# Programmable_DC_Load.net
KiCad netlist of a schematic drawn in EAGLE
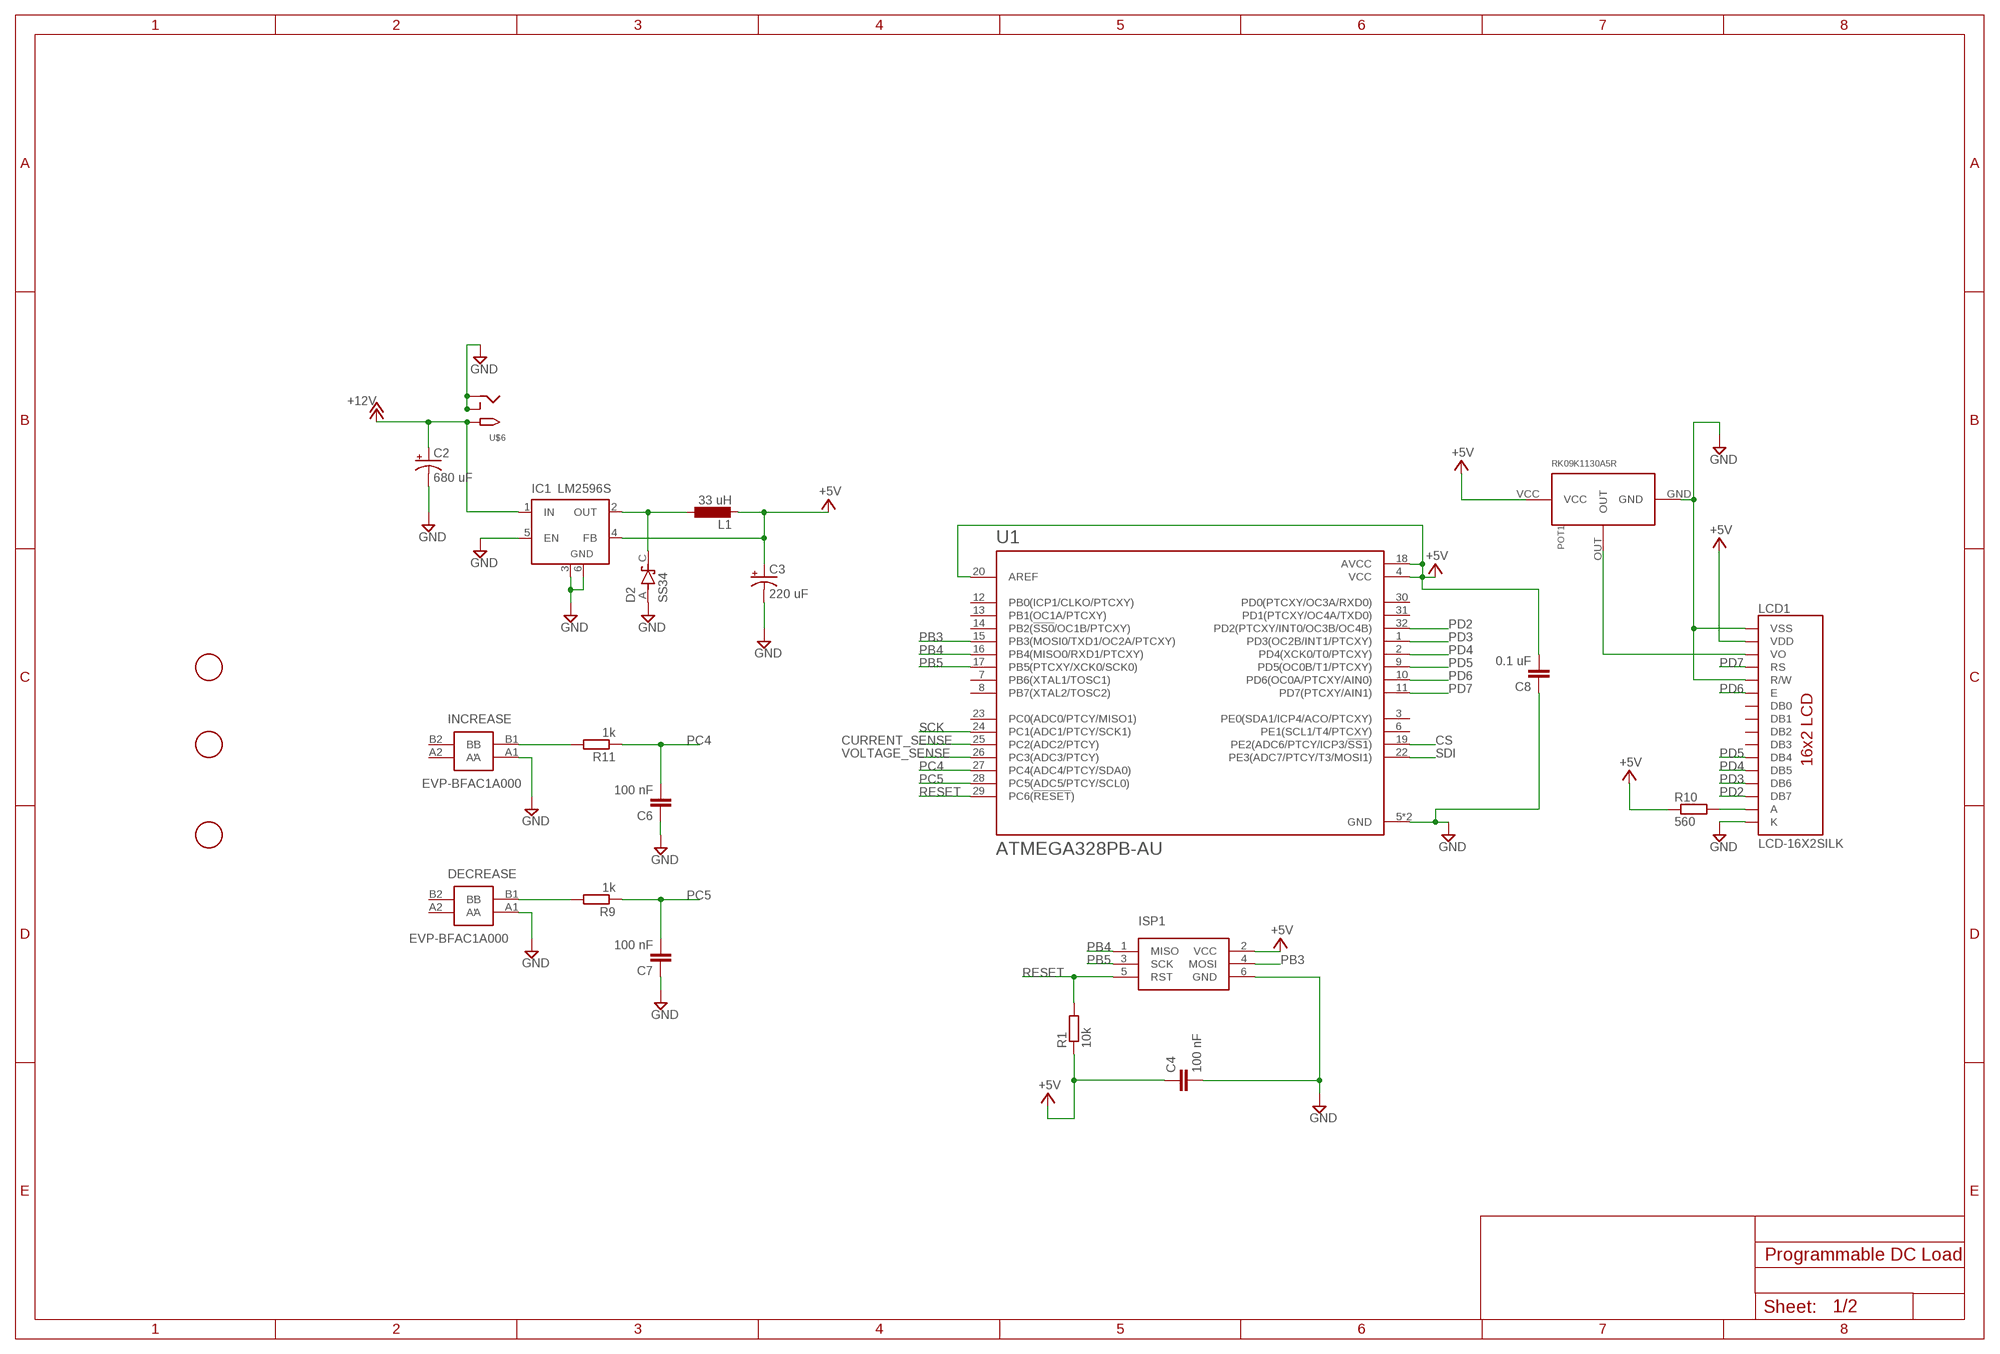
[diagram p0: schematic, sheet 1]
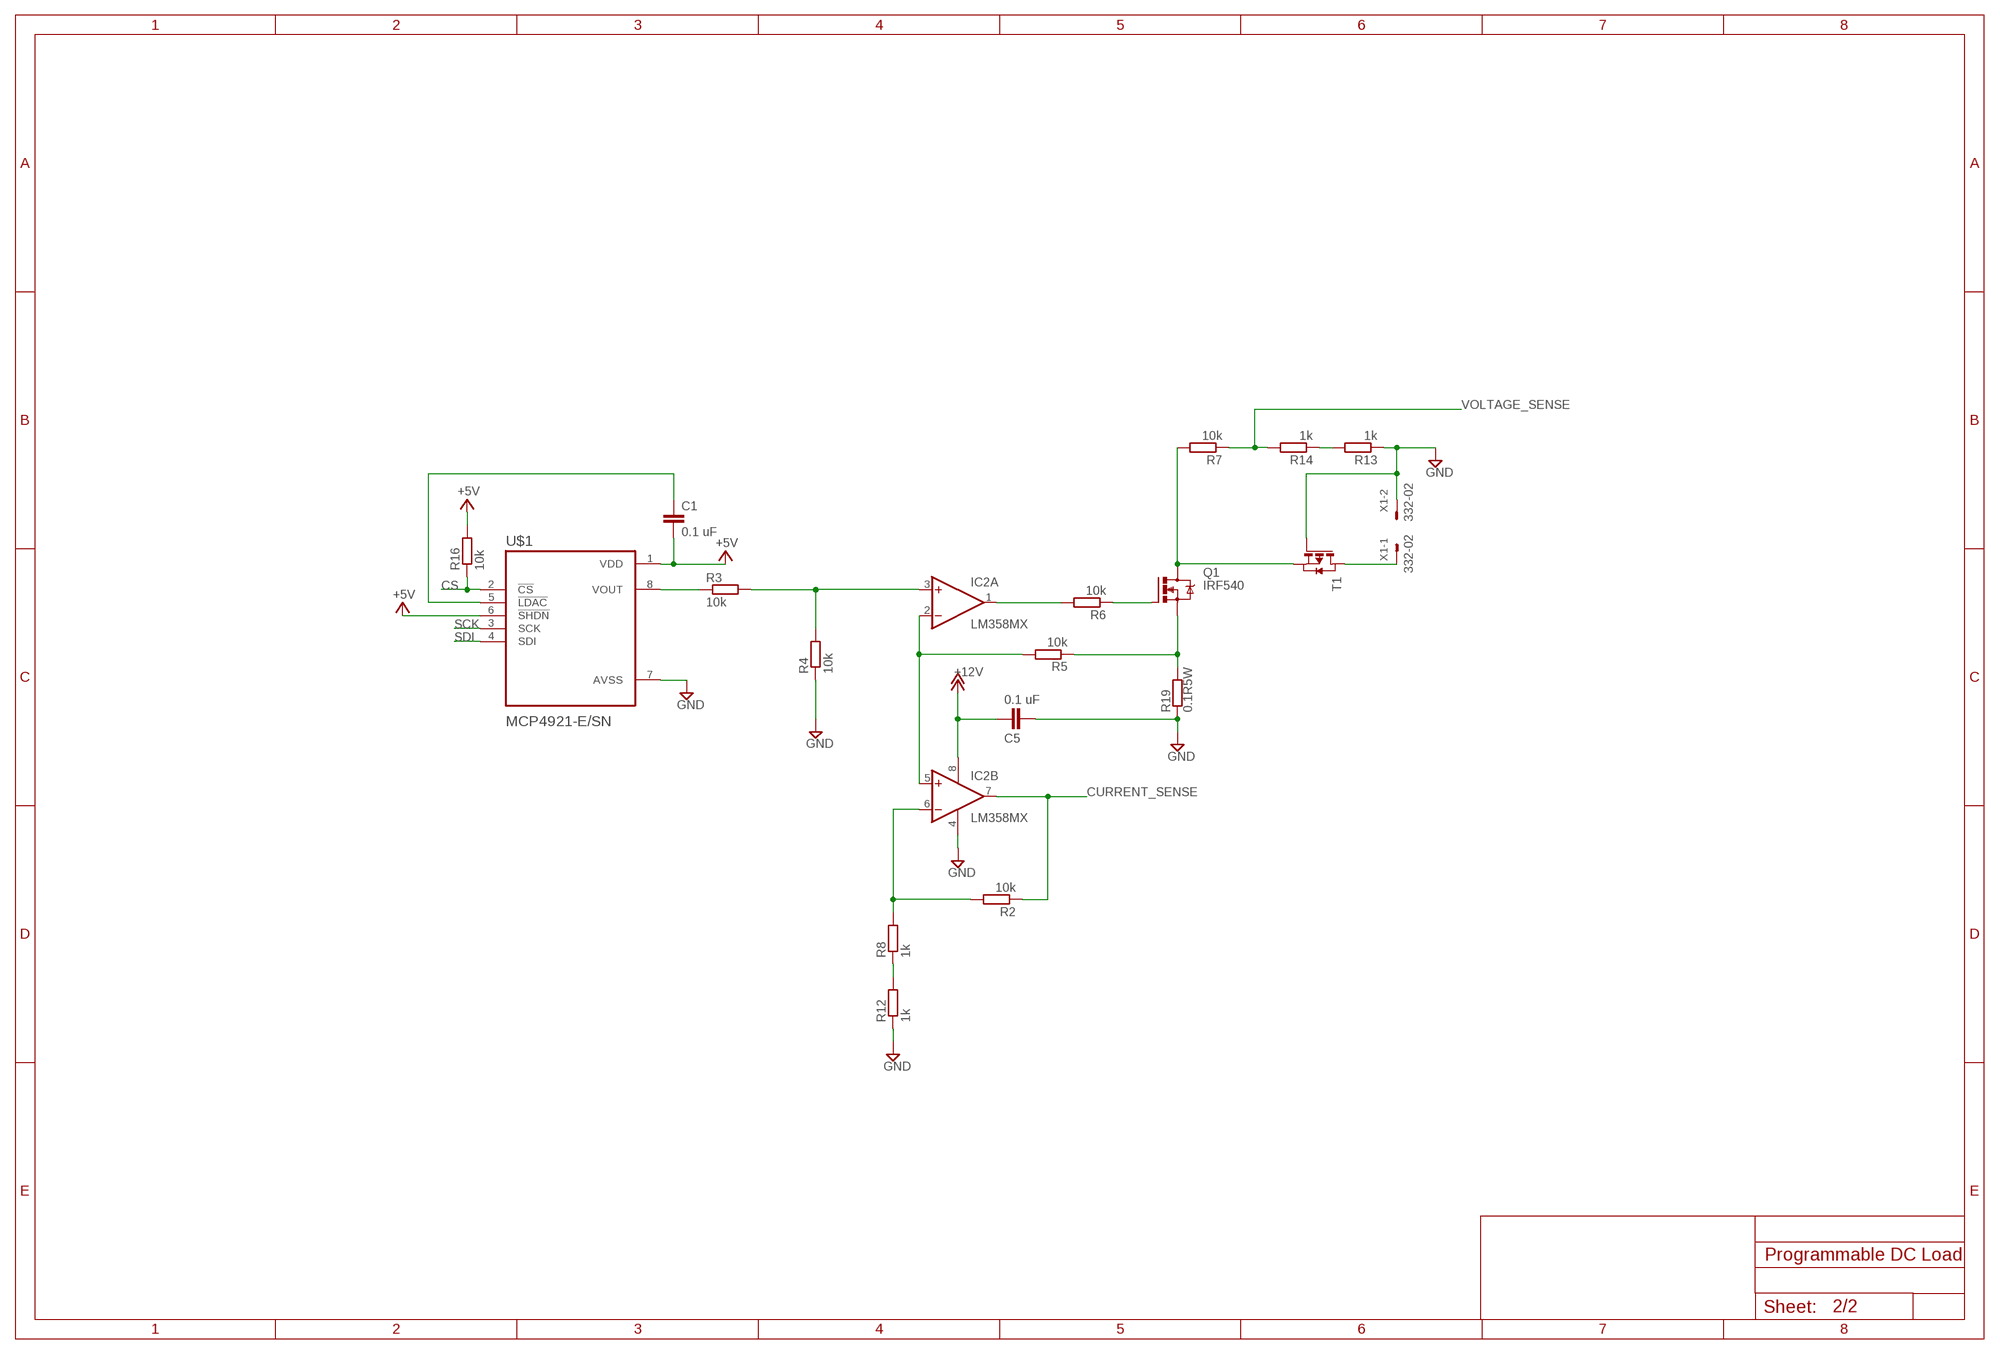
[diagram p1: schematic, sheet 2]

(export (version "E")
  (design (tool "Eeschema 10.0.6"))
  (components
    (comp (ref "C1")
      (value "0.1 uF")
      (footprint "eagle-import:C0805")
      (libsource (lib "eagle-import") (part "C-EUC0805"))
    )
    (comp (ref "C5")
      (value "0.1 uF")
      (footprint "eagle-import:C0805")
      (libsource (lib "eagle-import") (part "C-EUC0805"))
    )
    (comp (ref "IC2")
      (value "LM358MX")
      (footprint "eagle-import:SO08")
      (libsource (lib "eagle-import") (part "LM358MX"))
    )
    (comp (ref "Q1")
      (value "IRF540")
      (footprint "eagle-import:TO220BV")
      (libsource (lib "eagle-import") (part "IRF540"))
    )
    (comp (ref "R2")
      (value "10k")
      (footprint "eagle-import:R0805")
      (libsource (lib "eagle-import") (part "R-EU_R0805"))
    )
    (comp (ref "R3")
      (value "10k")
      (footprint "eagle-import:R0805")
      (libsource (lib "eagle-import") (part "R-EU_R0805"))
    )
    (comp (ref "R4")
      (value "10k")
      (footprint "eagle-import:R0805")
      (libsource (lib "eagle-import") (part "R-EU_R0805"))
    )
    (comp (ref "R5")
      (value "10k")
      (footprint "eagle-import:R0805")
      (libsource (lib "eagle-import") (part "R-EU_R0805"))
    )
    (comp (ref "R6")
      (value "10k")
      (footprint "eagle-import:R0805")
      (libsource (lib "eagle-import") (part "R-EU_R0805"))
    )
    (comp (ref "R7")
      (value "10k")
      (footprint "eagle-import:R0805")
      (libsource (lib "eagle-import") (part "R-EU_R0805"))
    )
    (comp (ref "R8")
      (value "1k")
      (footprint "eagle-import:R0805")
      (libsource (lib "eagle-import") (part "R-EU_R0805"))
    )
    (comp (ref "R12")
      (value "1k")
      (footprint "eagle-import:R0805")
      (libsource (lib "eagle-import") (part "R-EU_R0805"))
    )
    (comp (ref "R13")
      (value "1k")
      (footprint "eagle-import:R0805")
      (libsource (lib "eagle-import") (part "R-EU_R0805"))
    )
    (comp (ref "R14")
      (value "1k")
      (footprint "eagle-import:R0805")
      (libsource (lib "eagle-import") (part "R-EU_R0805"))
    )
    (comp (ref "R16")
      (value "10k")
      (footprint "eagle-import:R0805")
      (libsource (lib "eagle-import") (part "R-EU_R0805"))
    )
    (comp (ref "R19")
      (value "0.1R5W")
      (footprint "eagle-import:BVS")
      (libsource (lib "eagle-import") (part "BVS"))
    )
    (comp (ref "T1")
      (value "PMOSSOT23")
      (footprint "eagle-import:SOT-23")
      (libsource (lib "eagle-import") (part "PMOSSOT23"))
    )
    (comp (ref "U$1")
      (value "MCP4921-E/SN")
      (footprint "eagle-import:SOIC127P600X175-8N")
      (fields (field (name "MF") "Microchip"))
      (libsource (lib "eagle-import") (part "MCP4921-E/SN"))
    )
    (comp (ref "X1")
      (value "332-02")
      (footprint "eagle-import:332-02")
      (libsource (lib "eagle-import") (part "332-02"))
    )
    (comp (ref "C2")
      (value "680 uF")
      (footprint "eagle-import:140CLH-0810")
      (libsource (lib "eagle-import") (part "CPOL-US140CLH-0810"))
    )
    (comp (ref "C3")
      (value "220 uF")
      (footprint "eagle-import:140CLH-0810")
      (libsource (lib "eagle-import") (part "CPOL-US140CLH-0810"))
    )
    (comp (ref "C4")
      (value "100 nF")
      (footprint "eagle-import:C0805")
      (libsource (lib "eagle-import") (part "C-EUC0805"))
    )
    (comp (ref "C6")
      (value "100 nF")
      (footprint "eagle-import:C0805")
      (libsource (lib "eagle-import") (part "C-EUC0805"))
    )
    (comp (ref "C7")
      (value "100 nF")
      (footprint "eagle-import:C0805")
      (libsource (lib "eagle-import") (part "C-EUC0805"))
    )
    (comp (ref "C8")
      (value "0.1 uF")
      (footprint "eagle-import:C0805")
      (libsource (lib "eagle-import") (part "C-EUC0805"))
    )
    (comp (ref "D2")
      (value "SS34")
      (footprint "eagle-import:DIOM7959X265N")
      (fields (field (name "MF") "ON Semiconductor"))
      (libsource (lib "eagle-import") (part "SS34"))
    )
    (comp (ref "DECREASE")
      (value "EVP-BFAC1A000")
      (footprint "eagle-import:EVPBFAC1A000")
      (fields (field (name "MF") "Panasonic Electronic"))
      (libsource (lib "eagle-import") (part "EVP-BFAC1A000"))
    )
    (comp (ref "IC1")
      (value "LM2596S")
      (footprint "eagle-import:TO263-5")
      (libsource (lib "eagle-import") (part "LM2596S"))
    )
    (comp (ref "INCREASE")
      (value "EVP-BFAC1A000")
      (footprint "eagle-import:EVPBFAC1A000")
      (fields (field (name "MF") "Panasonic Electronic"))
      (libsource (lib "eagle-import") (part "EVP-BFAC1A000"))
    )
    (comp (ref "ISP1")
      (value "AVRISP-6")
      (footprint "eagle-import:AVRISP")
      (libsource (lib "eagle-import") (part "AVRISP-6"))
    )
    (comp (ref "L1")
      (value "33 uH")
      (footprint "eagle-import:L1812")
      (libsource (lib "eagle-import") (part "L-EUL1812"))
    )
    (comp (ref "LCD1")
      (value "LCD-16X2SILK")
      (footprint "eagle-import:LCD-16X2")
      (libsource (lib "eagle-import") (part "LCD-16X2SILK"))
    )
    (comp (ref "POT1")
      (value "RK09K1130A5R")
      (footprint "eagle-import:RK09K1130A5R")
      (libsource (lib "eagle-import") (part "RK09K1130A5R"))
    )
    (comp (ref "R1")
      (value "10k")
      (footprint "eagle-import:R0805")
      (libsource (lib "eagle-import") (part "R-EU_R0805"))
    )
    (comp (ref "R9")
      (value "1k")
      (footprint "eagle-import:R0805")
      (libsource (lib "eagle-import") (part "R-EU_R0805"))
    )
    (comp (ref "R10")
      (value "560")
      (footprint "eagle-import:R0805")
      (libsource (lib "eagle-import") (part "R-EU_R0805"))
    )
    (comp (ref "R11")
      (value "1k")
      (footprint "eagle-import:R0805")
      (libsource (lib "eagle-import") (part "R-EU_R0805"))
    )
    (comp (ref "U$2")
      (value "FIDUCIAL")
      (footprint "eagle-import:FIDUCIAL_1MM")
      (libsource (lib "eagle-import") (part "FIDUCIAL"))
    )
    (comp (ref "U$3")
      (value "FIDUCIAL")
      (footprint "eagle-import:FIDUCIAL_1MM")
      (libsource (lib "eagle-import") (part "FIDUCIAL"))
    )
    (comp (ref "U$4")
      (value "FIDUCIAL")
      (footprint "eagle-import:FIDUCIAL_1MM")
      (libsource (lib "eagle-import") (part "FIDUCIAL"))
    )
    (comp (ref "U$6")
      (value "2.1MMJACKTHM")
      (footprint "eagle-import:PJ-102A")
      (libsource (lib "eagle-import") (part "2.1MMJACKTHM"))
    )
    (comp (ref "U1")
      (value "ATMEGA328PB-AU")
      (footprint "eagle-import:QFP80P900X900X120-32N")
      (fields (field (name "MF") "Microchip Technology / Atmel"))
      (libsource (lib "eagle-import") (part "ATMEGA328PB-AU"))
    )
  )
  (nets
    (net (code "1") (name "+5V") (class "Default")
      (node (ref "C1") (pin "2") (pinfunction "2_2") (pintype "passive"))
      (node (ref "C3") (pin "+") (pinfunction "+_+") (pintype "passive"))
      (node (ref "C4") (pin "1") (pinfunction "1_1") (pintype "passive"))
      (node (ref "C8") (pin "2") (pinfunction "2_2") (pintype "passive"))
      (node (ref "IC1") (pin "4") (pinfunction "FB_4") (pintype "input"))
      (node (ref "ISP1") (pin "2") (pinfunction "VCC_2") (pintype "power_in"))
      (node (ref "L1") (pin "2") (pinfunction "2_2") (pintype "passive"))
      (node (ref "LCD1") (pin "2") (pinfunction "VDD_2") (pintype "power_in"))
      (node (ref "POT1") (pin "VCC") (pinfunction "VCC_VCC") (pintype "bidirectional"))
      (node (ref "R1") (pin "1") (pinfunction "1_1") (pintype "passive"))
      (node (ref "R10") (pin "1") (pinfunction "1_1") (pintype "passive"))
      (node (ref "R16") (pin "2") (pinfunction "2_2") (pintype "passive"))
      (node (ref "U$1") (pin "1") (pinfunction "VDD_1") (pintype "power_in"))
      (node (ref "U$1") (pin "6") (pinfunction "~{SHDN}_6") (pintype "input"))
      (node (ref "U1") (pin "18") (pinfunction "AVCC_18") (pintype "power_in"))
      (node (ref "U1") (pin "20") (pinfunction "AREF_20") (pintype "input"))
      (node (ref "U1") (pin "4") (pinfunction "VCC_4") (pintype "power_in"))
    )
    (net (code "2") (name "+12V") (class "Default")
      (node (ref "C2") (pin "+") (pinfunction "+_+") (pintype "passive"))
      (node (ref "C5") (pin "2") (pinfunction "2_2") (pintype "passive"))
      (node (ref "IC1") (pin "1") (pinfunction "IN_1") (pintype "input"))
      (node (ref "IC2") (pin "8") (pinfunction "V+_8") (pintype "power_in"))
      (node (ref "U$6") (pin "TIP") (pinfunction "TIP_TIP") (pintype "bidirectional"))
    )
    (net (code "3") (name "CS") (class "Default")
      (node (ref "R16") (pin "1") (pinfunction "1_1") (pintype "passive"))
      (node (ref "U$1") (pin "2") (pinfunction "~{CS}_2") (pintype "input"))
      (node (ref "U1") (pin "19") (pinfunction "PE2(ADC6/PTCY/ICP3/~{SS1})_19") (pintype "bidirectional"))
    )
    (net (code "4") (name "CURRENT_SENSE") (class "Default")
      (node (ref "IC2") (pin "7") (pinfunction "OUT_7") (pintype "output"))
      (node (ref "R2") (pin "1") (pinfunction "1_1") (pintype "passive"))
      (node (ref "U1") (pin "25") (pinfunction "PC2(ADC2/PTCY)_25") (pintype "bidirectional"))
    )
    (net (code "5") (name "GND") (class "Default")
      (node (ref "C2") (pin "-") (pinfunction "-_-") (pintype "passive"))
      (node (ref "C3") (pin "-") (pinfunction "-_-") (pintype "passive"))
      (node (ref "C4") (pin "2") (pinfunction "2_2") (pintype "passive"))
      (node (ref "C5") (pin "1") (pinfunction "1_1") (pintype "passive"))
      (node (ref "C6") (pin "1") (pinfunction "1_1") (pintype "passive"))
      (node (ref "C7") (pin "1") (pinfunction "1_1") (pintype "passive"))
      (node (ref "C8") (pin "1") (pinfunction "1_1") (pintype "passive"))
      (node (ref "D2") (pin "A") (pinfunction "A_A") (pintype "passive"))
      (node (ref "DECREASE") (pin "A1") (pinfunction "A_A1") (pintype "bidirectional"))
      (node (ref "IC1") (pin "3") (pinfunction "GND_3") (pintype "power_in"))
      (node (ref "IC1") (pin "5") (pinfunction "EN_5") (pintype "input"))
      (node (ref "IC1") (pin "6") (pinfunction "GND_6") (pintype "power_in"))
      (node (ref "IC2") (pin "4") (pinfunction "V-_4") (pintype "power_in"))
      (node (ref "INCREASE") (pin "A1") (pinfunction "A_A1") (pintype "bidirectional"))
      (node (ref "ISP1") (pin "6") (pinfunction "GND_6") (pintype "power_in"))
      (node (ref "LCD1") (pin "1") (pinfunction "VSS_1") (pintype "power_in"))
      (node (ref "LCD1") (pin "16") (pinfunction "K_16") (pintype "power_in"))
      (node (ref "LCD1") (pin "5") (pinfunction "R/W_5") (pintype "input"))
      (node (ref "POT1") (pin "GND") (pinfunction "GND_GND") (pintype "bidirectional"))
      (node (ref "R12") (pin "1") (pinfunction "1_1") (pintype "passive"))
      (node (ref "R13") (pin "1") (pinfunction "1_1") (pintype "passive"))
      (node (ref "R19") (pin "2") (pinfunction "2_2") (pintype "passive"))
      (node (ref "R4") (pin "1") (pinfunction "1_1") (pintype "passive"))
      (node (ref "T1") (pin "3") (pinfunction "G_3") (pintype "passive"))
      (node (ref "U$1") (pin "7") (pinfunction "AVSS_7") (pintype "power_in"))
      (node (ref "U$6") (pin "RING") (pinfunction "RING_RING") (pintype "bidirectional"))
      (node (ref "U$6") (pin "RING_SW") (pinfunction "RING_SW_RING_SW") (pintype "bidirectional"))
      (node (ref "U1") (pin "21") (pinfunction "GND_21") (pintype "power_in"))
      (node (ref "U1") (pin "5") (pinfunction "GND_5") (pintype "power_in"))
      (node (ref "X1") (pin "2") (pinfunction "S_2") (pintype "passive"))
    )
    (net (code "6") (name "Net-(D2-K)") (class "Default")
      (node (ref "D2") (pin "C") (pinfunction "K_C") (pintype "passive"))
      (node (ref "IC1") (pin "2") (pinfunction "OUT_2") (pintype "output"))
      (node (ref "L1") (pin "1") (pinfunction "1_1") (pintype "passive"))
    )
    (net (code "7") (name "Net-(DECREASE-B)") (class "Default")
      (node (ref "DECREASE") (pin "B1") (pinfunction "B_B1") (pintype "bidirectional"))
      (node (ref "R9") (pin "2") (pinfunction "2_2") (pintype "passive"))
    )
    (net (code "8") (name "Net-(IC2A-+IN)") (class "Default")
      (node (ref "IC2") (pin "3") (pinfunction "+IN_3") (pintype "input"))
      (node (ref "R3") (pin "2") (pinfunction "2_2") (pintype "passive"))
      (node (ref "R4") (pin "2") (pinfunction "2_2") (pintype "passive"))
    )
    (net (code "9") (name "Net-(IC2A--IN)") (class "Default")
      (node (ref "IC2") (pin "2") (pinfunction "-IN_2") (pintype "input"))
      (node (ref "IC2") (pin "5") (pinfunction "+IN_5") (pintype "input"))
      (node (ref "R5") (pin "2") (pinfunction "2_2") (pintype "passive"))
    )
    (net (code "10") (name "Net-(IC2A-OUT)") (class "Default")
      (node (ref "IC2") (pin "1") (pinfunction "OUT_1") (pintype "output"))
      (node (ref "R6") (pin "2") (pinfunction "2_2") (pintype "passive"))
    )
    (net (code "11") (name "Net-(IC2B--IN)") (class "Default")
      (node (ref "IC2") (pin "6") (pinfunction "-IN_6") (pintype "input"))
      (node (ref "R2") (pin "2") (pinfunction "2_2") (pintype "passive"))
      (node (ref "R8") (pin "2") (pinfunction "2_2") (pintype "passive"))
    )
    (net (code "12") (name "Net-(INCREASE-B)") (class "Default")
      (node (ref "INCREASE") (pin "B1") (pinfunction "B_B1") (pintype "bidirectional"))
      (node (ref "R11") (pin "2") (pinfunction "2_2") (pintype "passive"))
    )
    (net (code "13") (name "Net-(LCD1-A)") (class "Default")
      (node (ref "LCD1") (pin "15") (pinfunction "A_15") (pintype "power_in"))
      (node (ref "R10") (pin "2") (pinfunction "2_2") (pintype "passive"))
    )
    (net (code "14") (name "Net-(LCD1-VO)") (class "Default")
      (node (ref "LCD1") (pin "3") (pinfunction "VO_3") (pintype "bidirectional"))
      (node (ref "POT1") (pin "OUT") (pinfunction "OUT_OUT") (pintype "bidirectional"))
    )
    (net (code "15") (name "Net-(Q1-PadG)") (class "Default")
      (node (ref "Q1") (pin "G") (pinfunction "G_G") (pintype "passive"))
      (node (ref "R6") (pin "1") (pinfunction "1_1") (pintype "passive"))
    )
    (net (code "16") (name "Net-(Q1-PadS)") (class "Default")
      (node (ref "Q1") (pin "S") (pinfunction "S_S") (pintype "passive"))
      (node (ref "R19") (pin "1") (pinfunction "1_1") (pintype "passive"))
      (node (ref "R5") (pin "1") (pinfunction "1_1") (pintype "passive"))
    )
    (net (code "17") (name "Net-(R12-Pad2)") (class "Default")
      (node (ref "R12") (pin "2") (pinfunction "2_2") (pintype "passive"))
      (node (ref "R8") (pin "1") (pinfunction "1_1") (pintype "passive"))
    )
    (net (code "18") (name "Net-(R13-Pad2)") (class "Default")
      (node (ref "R13") (pin "2") (pinfunction "2_2") (pintype "passive"))
      (node (ref "R14") (pin "1") (pinfunction "1_1") (pintype "passive"))
    )
    (net (code "19") (name "Net-(T1-D)") (class "Default")
      (node (ref "T1") (pin "1") (pinfunction "D_1") (pintype "passive"))
      (node (ref "X1") (pin "1") (pinfunction "S_1") (pintype "passive"))
    )
    (net (code "20") (name "Net-(T1-S)") (class "Default")
      (node (ref "Q1") (pin "D") (pinfunction "D_D") (pintype "passive"))
      (node (ref "R7") (pin "2") (pinfunction "2_2") (pintype "passive"))
      (node (ref "T1") (pin "2") (pinfunction "S_2") (pintype "passive"))
    )
    (net (code "21") (name "Net-(U$1-VOUT)") (class "Default")
      (node (ref "R3") (pin "1") (pinfunction "1_1") (pintype "passive"))
      (node (ref "U$1") (pin "8") (pinfunction "VOUT_8") (pintype "output"))
    )
    (net (code "22") (name "Net-(U$1-~{LDAC})") (class "Default")
      (node (ref "C1") (pin "1") (pinfunction "1_1") (pintype "passive"))
      (node (ref "U$1") (pin "5") (pinfunction "~{LDAC}_5") (pintype "input"))
    )
    (net (code "23") (name "PB3") (class "Default")
      (node (ref "ISP1") (pin "4") (pinfunction "MOSI_4") (pintype "output"))
      (node (ref "U1") (pin "15") (pinfunction "PB3(MOSI0/TXD1/OC2A/PTCXY)_15") (pintype "bidirectional"))
    )
    (net (code "24") (name "PB4") (class "Default")
      (node (ref "ISP1") (pin "1") (pinfunction "MISO_1") (pintype "input"))
      (node (ref "U1") (pin "16") (pinfunction "PB4(MISO0/RXD1/PTCXY)_16") (pintype "bidirectional"))
    )
    (net (code "25") (name "PB5") (class "Default")
      (node (ref "ISP1") (pin "3") (pinfunction "SCK_3") (pintype "output"))
      (node (ref "U1") (pin "17") (pinfunction "PB5(PTCXY/XCK0/SCK0)_17") (pintype "bidirectional"))
    )
    (net (code "26") (name "PC4") (class "Default")
      (node (ref "C6") (pin "2") (pinfunction "2_2") (pintype "passive"))
      (node (ref "R11") (pin "1") (pinfunction "1_1") (pintype "passive"))
      (node (ref "U1") (pin "27") (pinfunction "PC4(ADC4/PTCY/SDA0)_27") (pintype "bidirectional"))
    )
    (net (code "27") (name "PC5") (class "Default")
      (node (ref "C7") (pin "2") (pinfunction "2_2") (pintype "passive"))
      (node (ref "R9") (pin "1") (pinfunction "1_1") (pintype "passive"))
      (node (ref "U1") (pin "28") (pinfunction "PC5(ADC5/PTCY/SCL0)_28") (pintype "bidirectional"))
    )
    (net (code "28") (name "PD2") (class "Default")
      (node (ref "LCD1") (pin "14") (pinfunction "DB7_14") (pintype "bidirectional"))
      (node (ref "U1") (pin "32") (pinfunction "PD2(PTCXY/INT0/OC3B/OC4B)_32") (pintype "bidirectional"))
    )
    (net (code "29") (name "PD3") (class "Default")
      (node (ref "LCD1") (pin "13") (pinfunction "DB6_13") (pintype "bidirectional"))
      (node (ref "U1") (pin "1") (pinfunction "PD3(OC2B/INT1/PTCXY)_1") (pintype "bidirectional"))
    )
    (net (code "30") (name "PD4") (class "Default")
      (node (ref "LCD1") (pin "12") (pinfunction "DB5_12") (pintype "bidirectional"))
      (node (ref "U1") (pin "2") (pinfunction "PD4(XCK0/T0/PTCXY)_2") (pintype "bidirectional"))
    )
    (net (code "31") (name "PD5") (class "Default")
      (node (ref "LCD1") (pin "11") (pinfunction "DB4_11") (pintype "bidirectional"))
      (node (ref "U1") (pin "9") (pinfunction "PD5(OC0B/T1/PTCXY)_9") (pintype "bidirectional"))
    )
    (net (code "32") (name "PD6") (class "Default")
      (node (ref "LCD1") (pin "6") (pinfunction "E_6") (pintype "input"))
      (node (ref "U1") (pin "10") (pinfunction "PD6(OC0A/PTCXY/AIN0)_10") (pintype "bidirectional"))
    )
    (net (code "33") (name "PD7") (class "Default")
      (node (ref "LCD1") (pin "4") (pinfunction "RS_4") (pintype "input"))
      (node (ref "U1") (pin "11") (pinfunction "PD7(PTCXY/AIN1)_11") (pintype "bidirectional"))
    )
    (net (code "34") (name "RESET") (class "Default")
      (node (ref "ISP1") (pin "5") (pinfunction "RST_5") (pintype "output"))
      (node (ref "R1") (pin "2") (pinfunction "2_2") (pintype "passive"))
      (node (ref "U1") (pin "29") (pinfunction "PC6(~{RESET})_29") (pintype "bidirectional"))
    )
    (net (code "35") (name "SCK") (class "Default")
      (node (ref "U$1") (pin "3") (pinfunction "SCK_3") (pintype "input"))
      (node (ref "U1") (pin "24") (pinfunction "PC1(ADC1/PTCY/SCK1)_24") (pintype "bidirectional"))
    )
    (net (code "36") (name "SDI") (class "Default")
      (node (ref "U$1") (pin "4") (pinfunction "SDI_4") (pintype "input"))
      (node (ref "U1") (pin "22") (pinfunction "PE3(ADC7/PTCY/T3/MOSI1)_22") (pintype "bidirectional"))
    )
    (net (code "37") (name "VOLTAGE_SENSE") (class "Default")
      (node (ref "R14") (pin "2") (pinfunction "2_2") (pintype "passive"))
      (node (ref "R7") (pin "1") (pinfunction "1_1") (pintype "passive"))
      (node (ref "U1") (pin "26") (pinfunction "PC3(ADC3/PTCY)_26") (pintype "bidirectional"))
    )
    (net (code "38") (name "unconnected-(DECREASE-A'-PadA2)") (class "Default")
      (node (ref "DECREASE") (pin "A2") (pinfunction "A'_A2") (pintype "bidirectional"))
    )
    (net (code "39") (name "unconnected-(DECREASE-B'-PadB2)") (class "Default")
      (node (ref "DECREASE") (pin "B2") (pinfunction "B'_B2") (pintype "bidirectional"))
    )
    (net (code "40") (name "unconnected-(INCREASE-A'-PadA2)") (class "Default")
      (node (ref "INCREASE") (pin "A2") (pinfunction "A'_A2") (pintype "bidirectional"))
    )
    (net (code "41") (name "unconnected-(INCREASE-B'-PadB2)") (class "Default")
      (node (ref "INCREASE") (pin "B2") (pinfunction "B'_B2") (pintype "bidirectional"))
    )
    (net (code "42") (name "unconnected-(LCD1-DB0-Pad7)") (class "Default")
      (node (ref "LCD1") (pin "7") (pinfunction "DB0_7") (pintype "bidirectional"))
    )
    (net (code "43") (name "unconnected-(LCD1-DB1-Pad8)") (class "Default")
      (node (ref "LCD1") (pin "8") (pinfunction "DB1_8") (pintype "bidirectional"))
    )
    (net (code "44") (name "unconnected-(LCD1-DB2-Pad9)") (class "Default")
      (node (ref "LCD1") (pin "9") (pinfunction "DB2_9") (pintype "bidirectional"))
    )
    (net (code "45") (name "unconnected-(LCD1-DB3-Pad10)") (class "Default")
      (node (ref "LCD1") (pin "10") (pinfunction "DB3_10") (pintype "bidirectional"))
    )
    (net (code "46") (name "unconnected-(U1-PB0(ICP1{slash}CLKO{slash}PTCXY)-Pad12)") (class "Default")
      (node (ref "U1") (pin "12") (pinfunction "PB0(ICP1/CLKO/PTCXY)_12") (pintype "bidirectional"))
    )
    (net (code "47") (name "unconnected-(U1-PB1(OC1A{slash}PTCXY)-Pad13)") (class "Default")
      (node (ref "U1") (pin "13") (pinfunction "PB1(OC1A/PTCXY)_13") (pintype "bidirectional"))
    )
    (net (code "48") (name "unconnected-(U1-PB2(~{SS0}{slash}OC1B{slash}PTCXY)-Pad14)") (class "Default")
      (node (ref "U1") (pin "14") (pinfunction "PB2(~{SS0}/OC1B/PTCXY)_14") (pintype "bidirectional"))
    )
    (net (code "49") (name "unconnected-(U1-PB6(XTAL1{slash}TOSC1)-Pad7)") (class "Default")
      (node (ref "U1") (pin "7") (pinfunction "PB6(XTAL1/TOSC1)_7") (pintype "bidirectional"))
    )
    (net (code "50") (name "unconnected-(U1-PB7(XTAL2{slash}TOSC2)-Pad8)") (class "Default")
      (node (ref "U1") (pin "8") (pinfunction "PB7(XTAL2/TOSC2)_8") (pintype "bidirectional"))
    )
    (net (code "51") (name "unconnected-(U1-PC0(ADC0{slash}PTCY{slash}MISO1)-Pad23)") (class "Default")
      (node (ref "U1") (pin "23") (pinfunction "PC0(ADC0/PTCY/MISO1)_23") (pintype "bidirectional"))
    )
    (net (code "52") (name "unconnected-(U1-PD0(PTCXY{slash}OC3A{slash}RXD0)-Pad30)") (class "Default")
      (node (ref "U1") (pin "30") (pinfunction "PD0(PTCXY/OC3A/RXD0)_30") (pintype "bidirectional"))
    )
    (net (code "53") (name "unconnected-(U1-PD1(PTCXY{slash}OC4A{slash}TXD0)-Pad31)") (class "Default")
      (node (ref "U1") (pin "31") (pinfunction "PD1(PTCXY/OC4A/TXD0)_31") (pintype "bidirectional"))
    )
    (net (code "54") (name "unconnected-(U1-PE0(SDA1{slash}ICP4{slash}ACO{slash}PTCXY)-Pad3)") (class "Default")
      (node (ref "U1") (pin "3") (pinfunction "PE0(SDA1/ICP4/ACO/PTCXY)_3") (pintype "bidirectional"))
    )
    (net (code "55") (name "unconnected-(U1-PE1(SCL1{slash}T4{slash}PTCXY)-Pad6)") (class "Default")
      (node (ref "U1") (pin "6") (pinfunction "PE1(SCL1/T4/PTCXY)_6") (pintype "bidirectional"))
    )
  )
)
